# schematic.net
KiCad netlist of a schematic drawn in EAGLE
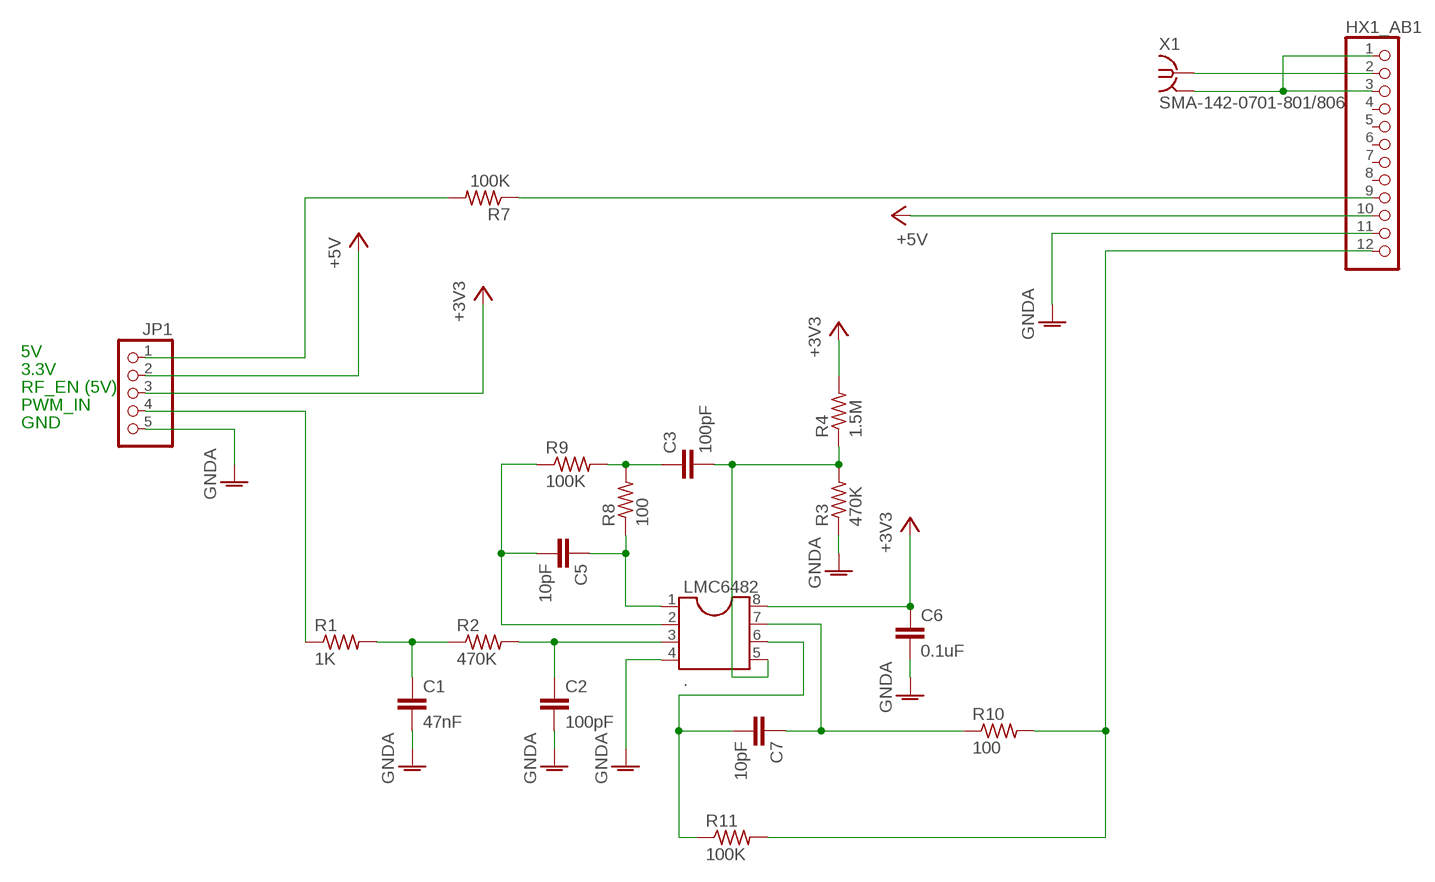
[diagram p0: schematic, sheet 1]

(export (version "E")
  (design (tool "Eeschema 10.0.6"))
  (components
    (comp (ref "C1")
      (value "47nF")
      (footprint "eagle-import:C2.5-2")
      (libsource (lib "eagle-import") (part "C2.5/2"))
    )
    (comp (ref "C2")
      (value "100pF")
      (footprint "eagle-import:C2.5-2")
      (libsource (lib "eagle-import") (part "C2.5/2"))
    )
    (comp (ref "C3")
      (value "100pF")
      (footprint "eagle-import:C2.5-2")
      (libsource (lib "eagle-import") (part "C2.5/2"))
    )
    (comp (ref "C5")
      (value "10pF")
      (footprint "eagle-import:C2.5-2")
      (libsource (lib "eagle-import") (part "C2.5/2"))
    )
    (comp (ref "C6")
      (value "0.1uF")
      (footprint "eagle-import:C2.5-2")
      (libsource (lib "eagle-import") (part "C2.5/2"))
    )
    (comp (ref "C7")
      (value "10pF")
      (footprint "eagle-import:C2.5-2")
      (libsource (lib "eagle-import") (part "C2.5/2"))
    )
    (comp (ref "HX1_AB1")
      (value "PINHD-1X12")
      (footprint "eagle-import:1X12")
      (libsource (lib "eagle-import") (part "PINHD-1X12"))
    )
    (comp (ref "JP1")
      (value "PINHD-1X5")
      (footprint "eagle-import:1X05")
      (libsource (lib "eagle-import") (part "PINHD-1X5"))
    )
    (comp (ref "LMC6482")
      (value ".")
      (footprint "eagle-import:DIL08")
      (libsource (lib "eagle-import") (part "DIL8"))
    )
    (comp (ref "R1")
      (value "1K")
      (footprint "eagle-import:0204V")
      (libsource (lib "eagle-import") (part "R-US_0204/2V"))
    )
    (comp (ref "R2")
      (value "470K")
      (footprint "eagle-import:0204V")
      (libsource (lib "eagle-import") (part "R-US_0204/2V"))
    )
    (comp (ref "R3")
      (value "470K")
      (footprint "eagle-import:0204V")
      (libsource (lib "eagle-import") (part "R-US_0204/2V"))
    )
    (comp (ref "R4")
      (value "1.5M")
      (footprint "eagle-import:0204V")
      (libsource (lib "eagle-import") (part "R-US_0204/2V"))
    )
    (comp (ref "R7")
      (value "100K")
      (footprint "eagle-import:0204V")
      (libsource (lib "eagle-import") (part "R-US_0204/2V"))
    )
    (comp (ref "R8")
      (value "100")
      (footprint "eagle-import:0204V")
      (libsource (lib "eagle-import") (part "R-US_0204/2V"))
    )
    (comp (ref "R9")
      (value "100K")
      (footprint "eagle-import:0204V")
      (libsource (lib "eagle-import") (part "R-US_0204/2V"))
    )
    (comp (ref "R10")
      (value "100")
      (footprint "eagle-import:0204V")
      (libsource (lib "eagle-import") (part "R-US_0204/2V"))
    )
    (comp (ref "R11")
      (value "100K")
      (footprint "eagle-import:0204V")
      (libsource (lib "eagle-import") (part "R-US_0204/2V"))
    )
    (comp (ref "X1")
      (value "SMA-142-0701-801/806")
      (footprint "eagle-import:J502-ND-142-0701-801_806")
      (fields (field (name "MF") "JOHNSON COMPONENTS") (field (name "MPN") "142-0701-801"))
      (libsource (lib "eagle-import") (part "SMA-142-0701-801/806"))
    )
  )
  (nets
    (net (code "1") (name "+3V3") (class "Default")
      (node (ref "C6") (pin "1") (pinfunction "1_1") (pintype "passive"))
      (node (ref "JP1") (pin "3") (pinfunction "3_3") (pintype "passive"))
      (node (ref "LMC6482") (pin "8") (pinfunction "8_8") (pintype "passive"))
      (node (ref "R4") (pin "2") (pinfunction "2_2") (pintype "passive"))
    )
    (net (code "2") (name "+5V") (class "Default")
      (node (ref "HX1_AB1") (pin "10") (pinfunction "10_10") (pintype "passive"))
      (node (ref "JP1") (pin "2") (pinfunction "2_2") (pintype "passive"))
    )
    (net (code "3") (name "GNDA") (class "Default")
      (node (ref "C1") (pin "2") (pinfunction "2_2") (pintype "passive"))
      (node (ref "C2") (pin "2") (pinfunction "2_2") (pintype "passive"))
      (node (ref "C6") (pin "2") (pinfunction "2_2") (pintype "passive"))
      (node (ref "HX1_AB1") (pin "11") (pinfunction "11_11") (pintype "passive"))
      (node (ref "JP1") (pin "5") (pinfunction "5_5") (pintype "passive"))
      (node (ref "LMC6482") (pin "4") (pinfunction "4_4") (pintype "passive"))
      (node (ref "R3") (pin "1") (pinfunction "1_1") (pintype "passive"))
    )
    (net (code "4") (name "Net-(C1-Pad1)") (class "Default")
      (node (ref "C1") (pin "1") (pinfunction "1_1") (pintype "passive"))
      (node (ref "R1") (pin "2") (pinfunction "2_2") (pintype "passive"))
      (node (ref "R2") (pin "1") (pinfunction "1_1") (pintype "passive"))
    )
    (net (code "5") (name "Net-(C2-Pad1)") (class "Default")
      (node (ref "C2") (pin "1") (pinfunction "1_1") (pintype "passive"))
      (node (ref "LMC6482") (pin "3") (pinfunction "3_3") (pintype "passive"))
      (node (ref "R2") (pin "2") (pinfunction "2_2") (pintype "passive"))
    )
    (net (code "6") (name "Net-(C3-Pad1)") (class "Default")
      (node (ref "C3") (pin "1") (pinfunction "1_1") (pintype "passive"))
      (node (ref "R8") (pin "2") (pinfunction "2_2") (pintype "passive"))
      (node (ref "R9") (pin "2") (pinfunction "2_2") (pintype "passive"))
    )
    (net (code "7") (name "Net-(C3-Pad2)") (class "Default")
      (node (ref "C3") (pin "2") (pinfunction "2_2") (pintype "passive"))
      (node (ref "LMC6482") (pin "5") (pinfunction "5_5") (pintype "passive"))
      (node (ref "R3") (pin "2") (pinfunction "2_2") (pintype "passive"))
      (node (ref "R4") (pin "1") (pinfunction "1_1") (pintype "passive"))
    )
    (net (code "8") (name "Net-(C5-Pad1)") (class "Default")
      (node (ref "C5") (pin "1") (pinfunction "1_1") (pintype "passive"))
      (node (ref "LMC6482") (pin "1") (pinfunction "1_1") (pintype "passive"))
      (node (ref "R8") (pin "1") (pinfunction "1_1") (pintype "passive"))
    )
    (net (code "9") (name "Net-(C5-Pad2)") (class "Default")
      (node (ref "C5") (pin "2") (pinfunction "2_2") (pintype "passive"))
      (node (ref "LMC6482") (pin "2") (pinfunction "2_2") (pintype "passive"))
      (node (ref "R9") (pin "1") (pinfunction "1_1") (pintype "passive"))
    )
    (net (code "10") (name "Net-(C7-Pad1)") (class "Default")
      (node (ref "C7") (pin "1") (pinfunction "1_1") (pintype "passive"))
      (node (ref "LMC6482") (pin "7") (pinfunction "7_7") (pintype "passive"))
      (node (ref "R10") (pin "1") (pinfunction "1_1") (pintype "passive"))
    )
    (net (code "11") (name "Net-(C7-Pad2)") (class "Default")
      (node (ref "C7") (pin "2") (pinfunction "2_2") (pintype "passive"))
      (node (ref "LMC6482") (pin "6") (pinfunction "6_6") (pintype "passive"))
      (node (ref "R11") (pin "1") (pinfunction "1_1") (pintype "passive"))
    )
    (net (code "12") (name "Net-(HX1_AB1-Pad1)") (class "Default")
      (node (ref "HX1_AB1") (pin "1") (pinfunction "1_1") (pintype "passive"))
      (node (ref "HX1_AB1") (pin "3") (pinfunction "3_3") (pintype "passive"))
      (node (ref "X1") (pin "G@1") (pinfunction "2_G@1") (pintype "passive"))
      (node (ref "X1") (pin "G@2") (pinfunction "2_G@2") (pintype "passive"))
      (node (ref "X1") (pin "G@3") (pinfunction "2_G@3") (pintype "passive"))
      (node (ref "X1") (pin "G@4") (pinfunction "2_G@4") (pintype "passive"))
    )
    (net (code "13") (name "Net-(HX1_AB1-Pad2)") (class "Default")
      (node (ref "HX1_AB1") (pin "2") (pinfunction "2_2") (pintype "passive"))
      (node (ref "X1") (pin "1") (pinfunction "1_1") (pintype "passive"))
    )
    (net (code "14") (name "Net-(HX1_AB1-Pad9)") (class "Default")
      (node (ref "HX1_AB1") (pin "9") (pinfunction "9_9") (pintype "passive"))
      (node (ref "R7") (pin "1") (pinfunction "1_1") (pintype "passive"))
    )
    (net (code "15") (name "Net-(HX1_AB1-Pad12)") (class "Default")
      (node (ref "HX1_AB1") (pin "12") (pinfunction "12_12") (pintype "passive"))
      (node (ref "R10") (pin "2") (pinfunction "2_2") (pintype "passive"))
      (node (ref "R11") (pin "2") (pinfunction "2_2") (pintype "passive"))
    )
    (net (code "16") (name "Net-(JP1-Pad1)") (class "Default")
      (node (ref "JP1") (pin "1") (pinfunction "1_1") (pintype "passive"))
      (node (ref "R7") (pin "2") (pinfunction "2_2") (pintype "passive"))
    )
    (net (code "17") (name "Net-(JP1-Pad4)") (class "Default")
      (node (ref "JP1") (pin "4") (pinfunction "4_4") (pintype "passive"))
      (node (ref "R1") (pin "1") (pinfunction "1_1") (pintype "passive"))
    )
    (net (code "18") (name "unconnected-(HX1_AB1-Pad4)") (class "Default")
      (node (ref "HX1_AB1") (pin "4") (pinfunction "4_4") (pintype "passive"))
    )
    (net (code "19") (name "unconnected-(HX1_AB1-Pad5)") (class "Default")
      (node (ref "HX1_AB1") (pin "5") (pinfunction "5_5") (pintype "passive"))
    )
    (net (code "20") (name "unconnected-(HX1_AB1-Pad6)") (class "Default")
      (node (ref "HX1_AB1") (pin "6") (pinfunction "6_6") (pintype "passive"))
    )
    (net (code "21") (name "unconnected-(HX1_AB1-Pad7)") (class "Default")
      (node (ref "HX1_AB1") (pin "7") (pinfunction "7_7") (pintype "passive"))
    )
    (net (code "22") (name "unconnected-(HX1_AB1-Pad8)") (class "Default")
      (node (ref "HX1_AB1") (pin "8") (pinfunction "8_8") (pintype "passive"))
    )
  )
)
